# CW308_K82_UFO.net
KiCad netlist of a schematic drawn in Altium Designer
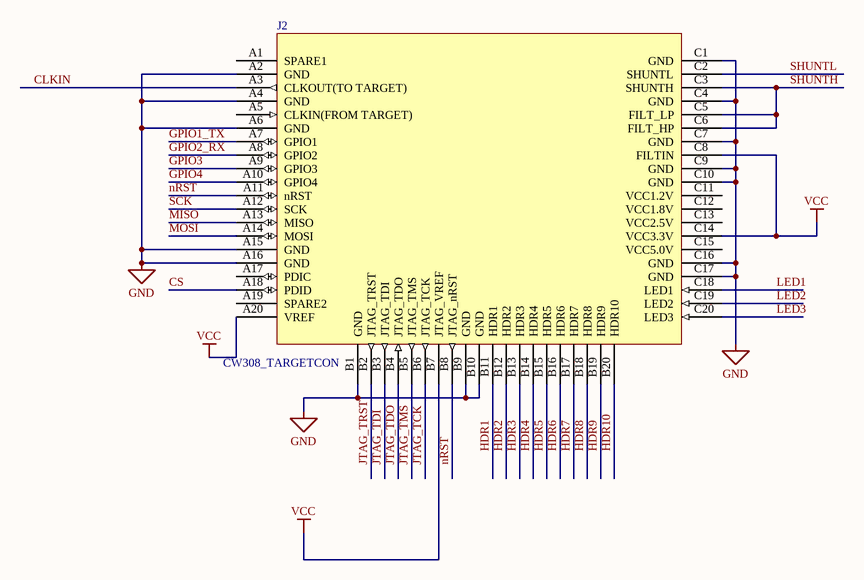
[diagram p0: CW308_K82_UFO.SchDoc]

(export (version "E")
  (design (tool "Eeschema 10.0.6"))
  (components
    (comp (ref "J2")
      (value "CW308_TARGETCON")
      (footprint "CW308_TBOARD_CONN")
      (description "CW308 \"Standard\" Target Board Connector")
      (fields (field (name "PART NUMBER") "CW308_TBOARD"))
      (libsource (lib "NewAE_AltiumLib") (part "CW308_TBOARD"))
    )
  )
  (nets
    (net (code "1") (name "/CLKIN") (class "Default")
      (node (ref "J2") (pin "A3") (pinfunction "CLKOUT(TO_TARGET)_A3") (pintype "output"))
    )
    (net (code "2") (name "/CS") (class "Default")
      (node (ref "J2") (pin "A18") (pinfunction "PDID_A18") (pintype "bidirectional"))
    )
    (net (code "3") (name "/GPIO1_TX") (class "Default")
      (node (ref "J2") (pin "A7") (pinfunction "GPIO1_A7") (pintype "bidirectional"))
    )
    (net (code "4") (name "/GPIO2_RX") (class "Default")
      (node (ref "J2") (pin "A8") (pinfunction "GPIO2_A8") (pintype "bidirectional"))
    )
    (net (code "5") (name "/GPIO3") (class "Default")
      (node (ref "J2") (pin "A9") (pinfunction "GPIO3_A9") (pintype "bidirectional"))
    )
    (net (code "6") (name "/GPIO4") (class "Default")
      (node (ref "J2") (pin "A10") (pinfunction "GPIO4_A10") (pintype "bidirectional"))
    )
    (net (code "7") (name "/HDR1") (class "Default")
      (node (ref "J2") (pin "B11") (pinfunction "HDR1_B11") (pintype "passive"))
    )
    (net (code "8") (name "/HDR2") (class "Default")
      (node (ref "J2") (pin "B12") (pinfunction "HDR2_B12") (pintype "passive"))
    )
    (net (code "9") (name "/HDR3") (class "Default")
      (node (ref "J2") (pin "B13") (pinfunction "HDR3_B13") (pintype "passive"))
    )
    (net (code "10") (name "/HDR4") (class "Default")
      (node (ref "J2") (pin "B14") (pinfunction "HDR4_B14") (pintype "passive"))
    )
    (net (code "11") (name "/HDR5") (class "Default")
      (node (ref "J2") (pin "B15") (pinfunction "HDR5_B15") (pintype "passive"))
    )
    (net (code "12") (name "/HDR6") (class "Default")
      (node (ref "J2") (pin "B16") (pinfunction "HDR6_B16") (pintype "passive"))
    )
    (net (code "13") (name "/HDR7") (class "Default")
      (node (ref "J2") (pin "B17") (pinfunction "HDR7_B17") (pintype "passive"))
    )
    (net (code "14") (name "/HDR8") (class "Default")
      (node (ref "J2") (pin "B18") (pinfunction "HDR8_B18") (pintype "passive"))
    )
    (net (code "15") (name "/HDR9") (class "Default")
      (node (ref "J2") (pin "B19") (pinfunction "HDR9_B19") (pintype "passive"))
    )
    (net (code "16") (name "/HDR10") (class "Default")
      (node (ref "J2") (pin "B20") (pinfunction "HDR10_B20") (pintype "passive"))
    )
    (net (code "17") (name "/JTAG_TCK") (class "Default")
      (node (ref "J2") (pin "B6") (pinfunction "JTAG_TCK_B6") (pintype "output"))
    )
    (net (code "18") (name "/JTAG_TDI") (class "Default")
      (node (ref "J2") (pin "B3") (pinfunction "JTAG_TDI_B3") (pintype "output"))
    )
    (net (code "19") (name "/JTAG_TDO") (class "Default")
      (node (ref "J2") (pin "B4") (pinfunction "JTAG_TDO_B4") (pintype "input"))
    )
    (net (code "20") (name "/JTAG_TMS") (class "Default")
      (node (ref "J2") (pin "B5") (pinfunction "JTAG_TMS_B5") (pintype "output"))
    )
    (net (code "21") (name "/JTAG_TRST") (class "Default")
      (node (ref "J2") (pin "B2") (pinfunction "JTAG_TRST_B2") (pintype "output"))
    )
    (net (code "22") (name "/LED1") (class "Default")
      (node (ref "J2") (pin "C18") (pinfunction "LED1_C18") (pintype "input"))
    )
    (net (code "23") (name "/LED2") (class "Default")
      (node (ref "J2") (pin "C19") (pinfunction "LED2_C19") (pintype "input"))
    )
    (net (code "24") (name "/LED3") (class "Default")
      (node (ref "J2") (pin "C20") (pinfunction "LED3_C20") (pintype "input"))
    )
    (net (code "25") (name "/MISO") (class "Default")
      (node (ref "J2") (pin "A13") (pinfunction "MISO_A13") (pintype "bidirectional"))
    )
    (net (code "26") (name "/MOSI") (class "Default")
      (node (ref "J2") (pin "A14") (pinfunction "MOSI_A14") (pintype "bidirectional"))
    )
    (net (code "27") (name "/SCK") (class "Default")
      (node (ref "J2") (pin "A12") (pinfunction "SCK_A12") (pintype "bidirectional"))
    )
    (net (code "28") (name "/SHUNTH") (class "Default")
      (node (ref "J2") (pin "C3") (pinfunction "SHUNTH_C3") (pintype "passive"))
      (node (ref "J2") (pin "C5") (pinfunction "FILT_LP_C5") (pintype "passive"))
      (node (ref "J2") (pin "C6") (pinfunction "FILT_HP_C6") (pintype "passive"))
    )
    (net (code "29") (name "/SHUNTL") (class "Default")
      (node (ref "J2") (pin "C2") (pinfunction "SHUNTL_C2") (pintype "passive"))
    )
    (net (code "30") (name "/nRST") (class "Default")
      (node (ref "J2") (pin "A11") (pinfunction "nRST_A11") (pintype "bidirectional"))
      (node (ref "J2") (pin "B8") (pinfunction "JTAG_nRST_B8") (pintype "output"))
    )
    (net (code "31") (name "GND") (class "Default")
      (node (ref "J2") (pin "A15") (pinfunction "GND_A15") (pintype "passive"))
      (node (ref "J2") (pin "A16") (pinfunction "GND_A16") (pintype "passive"))
      (node (ref "J2") (pin "A2") (pinfunction "GND_A2") (pintype "passive"))
      (node (ref "J2") (pin "A4") (pinfunction "GND_A4") (pintype "passive"))
      (node (ref "J2") (pin "A6") (pinfunction "GND_A6") (pintype "power_in"))
      (node (ref "J2") (pin "B1") (pinfunction "GND_B1") (pintype "passive"))
      (node (ref "J2") (pin "B10") (pinfunction "GND_B10") (pintype "passive"))
      (node (ref "J2") (pin "B9") (pinfunction "GND_B9") (pintype "passive"))
      (node (ref "J2") (pin "C1") (pinfunction "GND_C1") (pintype "power_in"))
      (node (ref "J2") (pin "C10") (pinfunction "GND_C10") (pintype "power_in"))
      (node (ref "J2") (pin "C16") (pinfunction "GND_C16") (pintype "power_in"))
      (node (ref "J2") (pin "C17") (pinfunction "GND_C17") (pintype "power_in"))
      (node (ref "J2") (pin "C4") (pinfunction "GND_C4") (pintype "power_in"))
      (node (ref "J2") (pin "C7") (pinfunction "GND_C7") (pintype "power_in"))
      (node (ref "J2") (pin "C9") (pinfunction "GND_C9") (pintype "power_in"))
    )
    (net (code "32") (name "VCC") (class "Default")
      (node (ref "J2") (pin "A20") (pinfunction "VREF_A20") (pintype "tri_state"))
      (node (ref "J2") (pin "B7") (pinfunction "JTAG_VREF_B7") (pintype "tri_state"))
      (node (ref "J2") (pin "C14") (pinfunction "VCC3.3V_C14") (pintype "power_in"))
      (node (ref "J2") (pin "C8") (pinfunction "FILTIN_C8") (pintype "passive"))
    )
    (net (code "33") (name "unconnected-(J2-CLKIN(FROM_TARGET)-PadA5)") (class "Default")
      (node (ref "J2") (pin "A5") (pinfunction "CLKIN(FROM_TARGET)_A5") (pintype "input"))
    )
    (net (code "34") (name "unconnected-(J2-PDIC-PadA17)") (class "Default")
      (node (ref "J2") (pin "A17") (pinfunction "PDIC_A17") (pintype "bidirectional"))
    )
    (net (code "35") (name "unconnected-(J2-SPARE1-PadA1)") (class "Default")
      (node (ref "J2") (pin "A1") (pinfunction "SPARE1_A1") (pintype "passive"))
    )
    (net (code "36") (name "unconnected-(J2-SPARE2-PadA19)") (class "Default")
      (node (ref "J2") (pin "A19") (pinfunction "SPARE2_A19") (pintype "passive"))
    )
    (net (code "37") (name "unconnected-(J2-VCC1.2V-PadC11)") (class "Default")
      (node (ref "J2") (pin "C11") (pinfunction "VCC1.2V_C11") (pintype "power_in"))
    )
    (net (code "38") (name "unconnected-(J2-VCC1.8V-PadC12)") (class "Default")
      (node (ref "J2") (pin "C12") (pinfunction "VCC1.8V_C12") (pintype "power_in"))
    )
    (net (code "39") (name "unconnected-(J2-VCC2.5V-PadC13)") (class "Default")
      (node (ref "J2") (pin "C13") (pinfunction "VCC2.5V_C13") (pintype "power_in"))
    )
    (net (code "40") (name "unconnected-(J2-VCC5.0V-PadC15)") (class "Default")
      (node (ref "J2") (pin "C15") (pinfunction "VCC5.0V_C15") (pintype "power_in"))
    )
  )
)
